# ADXL345_Breakout-v14.net
KiCad netlist of a schematic drawn in EAGLE
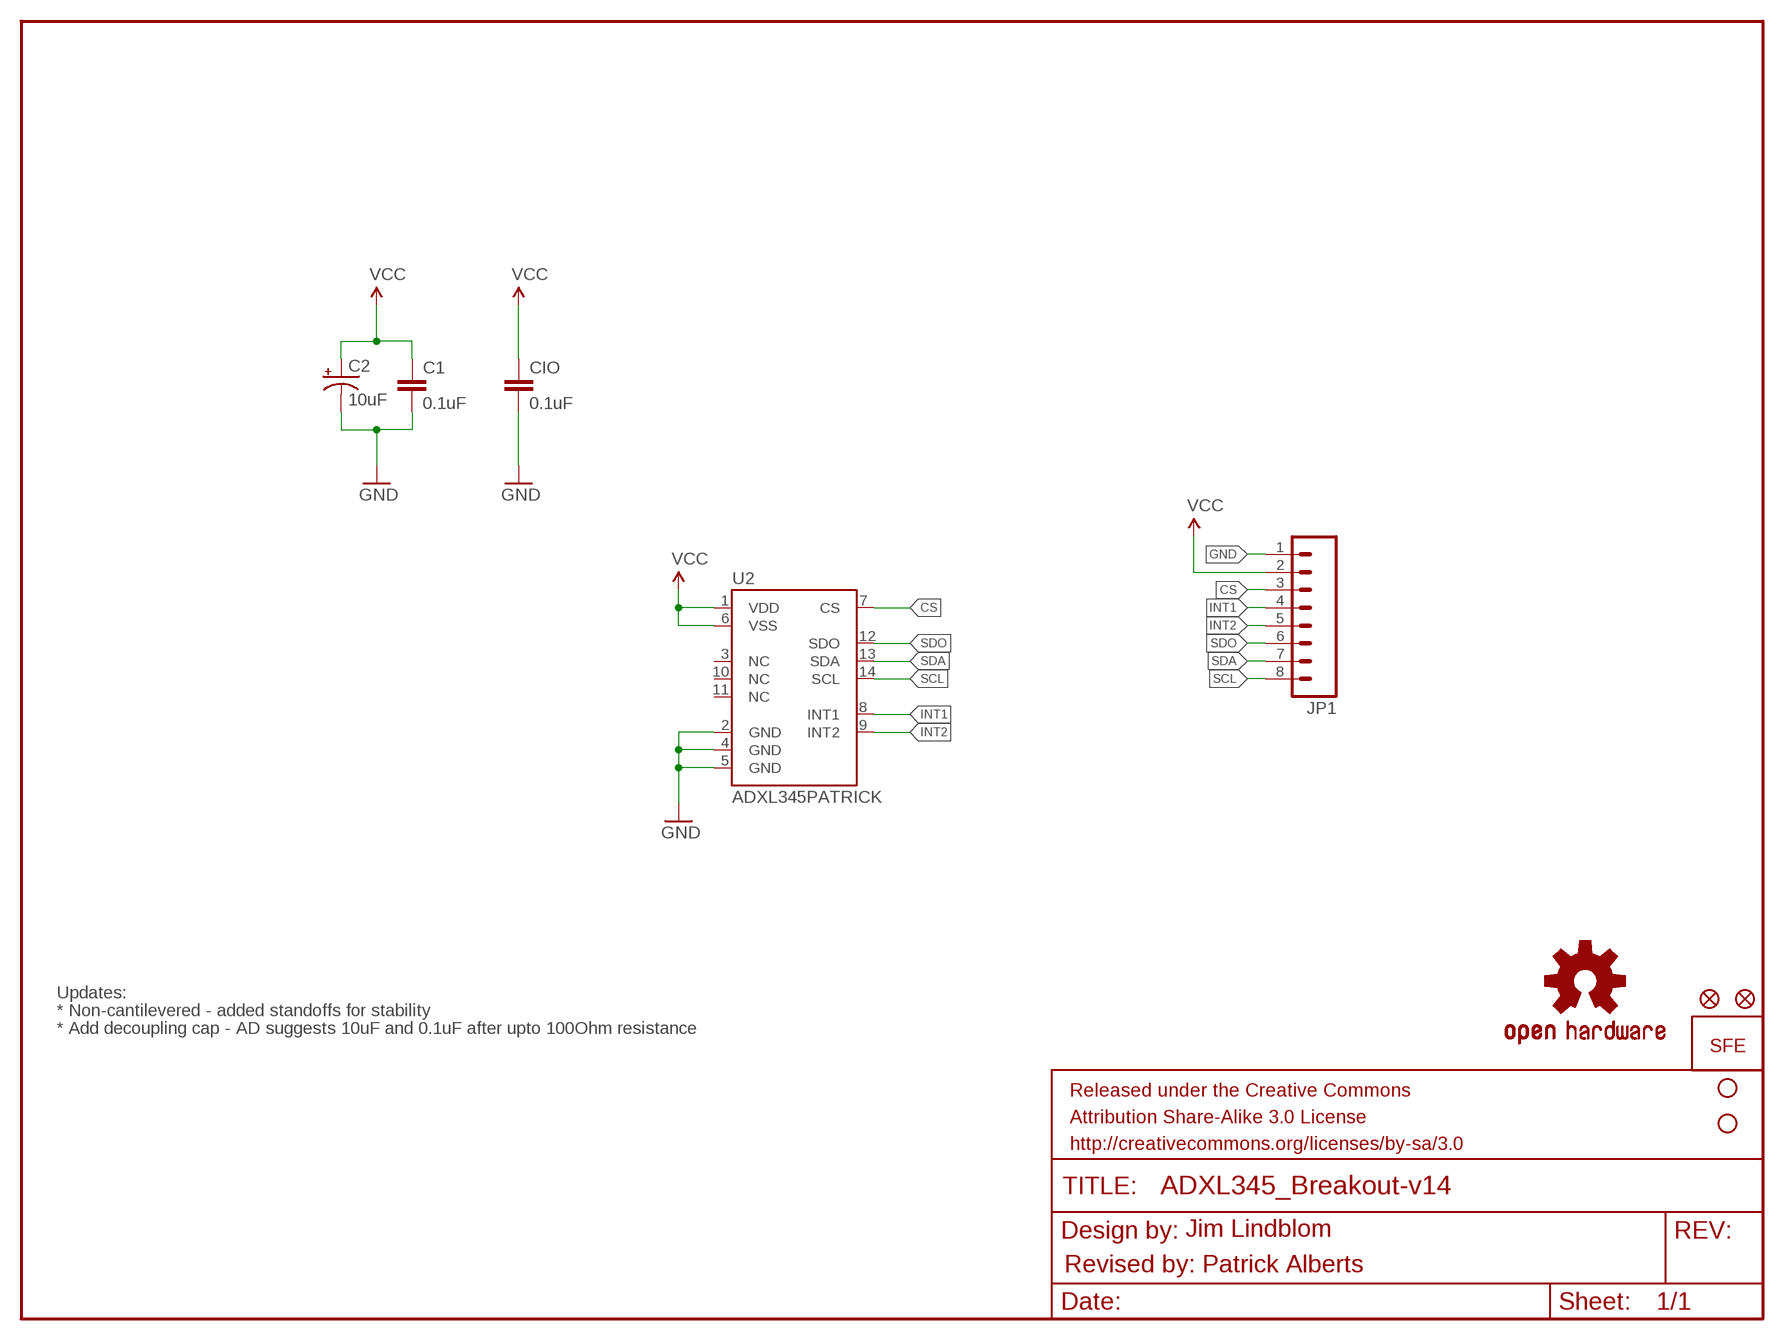
[diagram p0: schematic, sheet 1]

(export (version "E")
  (design (tool "Eeschema 10.0.6"))
  (components
    (comp (ref "C1")
      (value "0.1uF")
      (footprint "eagle-import:0603-CAP")
      (libsource (lib "eagle-import") (part "CAP0603-CAP"))
    )
    (comp (ref "C2")
      (value "10uF")
      (footprint "eagle-import:EIA3216")
      (libsource (lib "eagle-import") (part "CAP_POL1206"))
    )
    (comp (ref "CIO")
      (value "0.1uF")
      (footprint "eagle-import:0603-CAP")
      (libsource (lib "eagle-import") (part "CAP0603-CAP"))
    )
    (comp (ref "JP1")
      (value "M08")
      (footprint "eagle-import:1X08")
      (libsource (lib "eagle-import") (part "M08"))
    )
    (comp (ref "JP2")
      (value "STAND-OFF")
      (footprint "eagle-import:STAND-OFF")
      (libsource (lib "eagle-import") (part "STAND-OFF"))
    )
    (comp (ref "JP3")
      (value "STAND-OFF")
      (footprint "eagle-import:STAND-OFF")
      (libsource (lib "eagle-import") (part "STAND-OFF"))
    )
    (comp (ref "JP4")
      (value "FIDUCIAL1X2")
      (footprint "eagle-import:FIDUCIAL-1X2")
      (libsource (lib "eagle-import") (part "FIDUCIAL1X2"))
    )
    (comp (ref "JP5")
      (value "FIDUCIAL1X2")
      (footprint "eagle-import:FIDUCIAL-1X2")
      (libsource (lib "eagle-import") (part "FIDUCIAL1X2"))
    )
    (comp (ref "U$2")
      (value "LOGO-SFENEW")
      (footprint "eagle-import:SFE-NEW-WEBLOGO")
      (libsource (lib "eagle-import") (part "LOGO-SFENEW"))
    )
    (comp (ref "U$3")
      (value "OSHW-LOGOS")
      (footprint "eagle-import:OSHW-LOGO-S")
      (libsource (lib "eagle-import") (part "OSHW-LOGOS"))
    )
    (comp (ref "U2")
      (value "ADXL345PATRICK")
      (footprint "eagle-import:LGA14_1_1_PATRICK")
      (libsource (lib "eagle-import") (part "ADXL345PATRICK"))
    )
  )
  (nets
    (net (code "1") (name "CS") (class "Default")
      (node (ref "JP1") (pin "3") (pinfunction "3_3") (pintype "passive"))
      (node (ref "U2") (pin "7") (pinfunction "CS_7") (pintype "bidirectional"))
    )
    (net (code "2") (name "GND") (class "Default")
      (node (ref "C1") (pin "2") (pinfunction "2_2") (pintype "passive"))
      (node (ref "C2") (pin "C") (pinfunction "-_C") (pintype "passive"))
      (node (ref "CIO") (pin "2") (pinfunction "2_2") (pintype "passive"))
      (node (ref "JP1") (pin "1") (pinfunction "1_1") (pintype "passive"))
      (node (ref "U2") (pin "2") (pinfunction "GND_2") (pintype "bidirectional"))
      (node (ref "U2") (pin "4") (pinfunction "GND_4") (pintype "bidirectional"))
      (node (ref "U2") (pin "5") (pinfunction "GND_5") (pintype "bidirectional"))
    )
    (net (code "3") (name "INT1") (class "Default")
      (node (ref "JP1") (pin "4") (pinfunction "4_4") (pintype "passive"))
      (node (ref "U2") (pin "8") (pinfunction "INT1_8") (pintype "bidirectional"))
    )
    (net (code "4") (name "INT2") (class "Default")
      (node (ref "JP1") (pin "5") (pinfunction "5_5") (pintype "passive"))
      (node (ref "U2") (pin "9") (pinfunction "INT2_9") (pintype "bidirectional"))
    )
    (net (code "5") (name "SCL") (class "Default")
      (node (ref "JP1") (pin "8") (pinfunction "8_8") (pintype "passive"))
      (node (ref "U2") (pin "14") (pinfunction "SCL_14") (pintype "bidirectional"))
    )
    (net (code "6") (name "SDA") (class "Default")
      (node (ref "JP1") (pin "7") (pinfunction "7_7") (pintype "passive"))
      (node (ref "U2") (pin "13") (pinfunction "SDA_13") (pintype "bidirectional"))
    )
    (net (code "7") (name "SDO") (class "Default")
      (node (ref "JP1") (pin "6") (pinfunction "6_6") (pintype "passive"))
      (node (ref "U2") (pin "12") (pinfunction "SDO_12") (pintype "bidirectional"))
    )
    (net (code "8") (name "VCC") (class "Default")
      (node (ref "C1") (pin "1") (pinfunction "1_1") (pintype "passive"))
      (node (ref "C2") (pin "A") (pinfunction "+_A") (pintype "passive"))
      (node (ref "CIO") (pin "1") (pinfunction "1_1") (pintype "passive"))
      (node (ref "JP1") (pin "2") (pinfunction "2_2") (pintype "passive"))
      (node (ref "U2") (pin "1") (pinfunction "VDD_1") (pintype "bidirectional"))
      (node (ref "U2") (pin "6") (pinfunction "VSS_6") (pintype "bidirectional"))
    )
    (net (code "9") (name "unconnected-(U2-NC-Pad3)") (class "Default")
      (node (ref "U2") (pin "3") (pinfunction "NC_3") (pintype "bidirectional"))
    )
    (net (code "10") (name "unconnected-(U2-NC-Pad10)") (class "Default")
      (node (ref "U2") (pin "10") (pinfunction "NC_10") (pintype "bidirectional"))
    )
    (net (code "11") (name "unconnected-(U2-NC-Pad11)") (class "Default")
      (node (ref "U2") (pin "11") (pinfunction "NC_11") (pintype "bidirectional"))
    )
  )
)
